# AUDIO_AMP_NB2B.net
KiCad netlist of a schematic drawn in Altium Designer
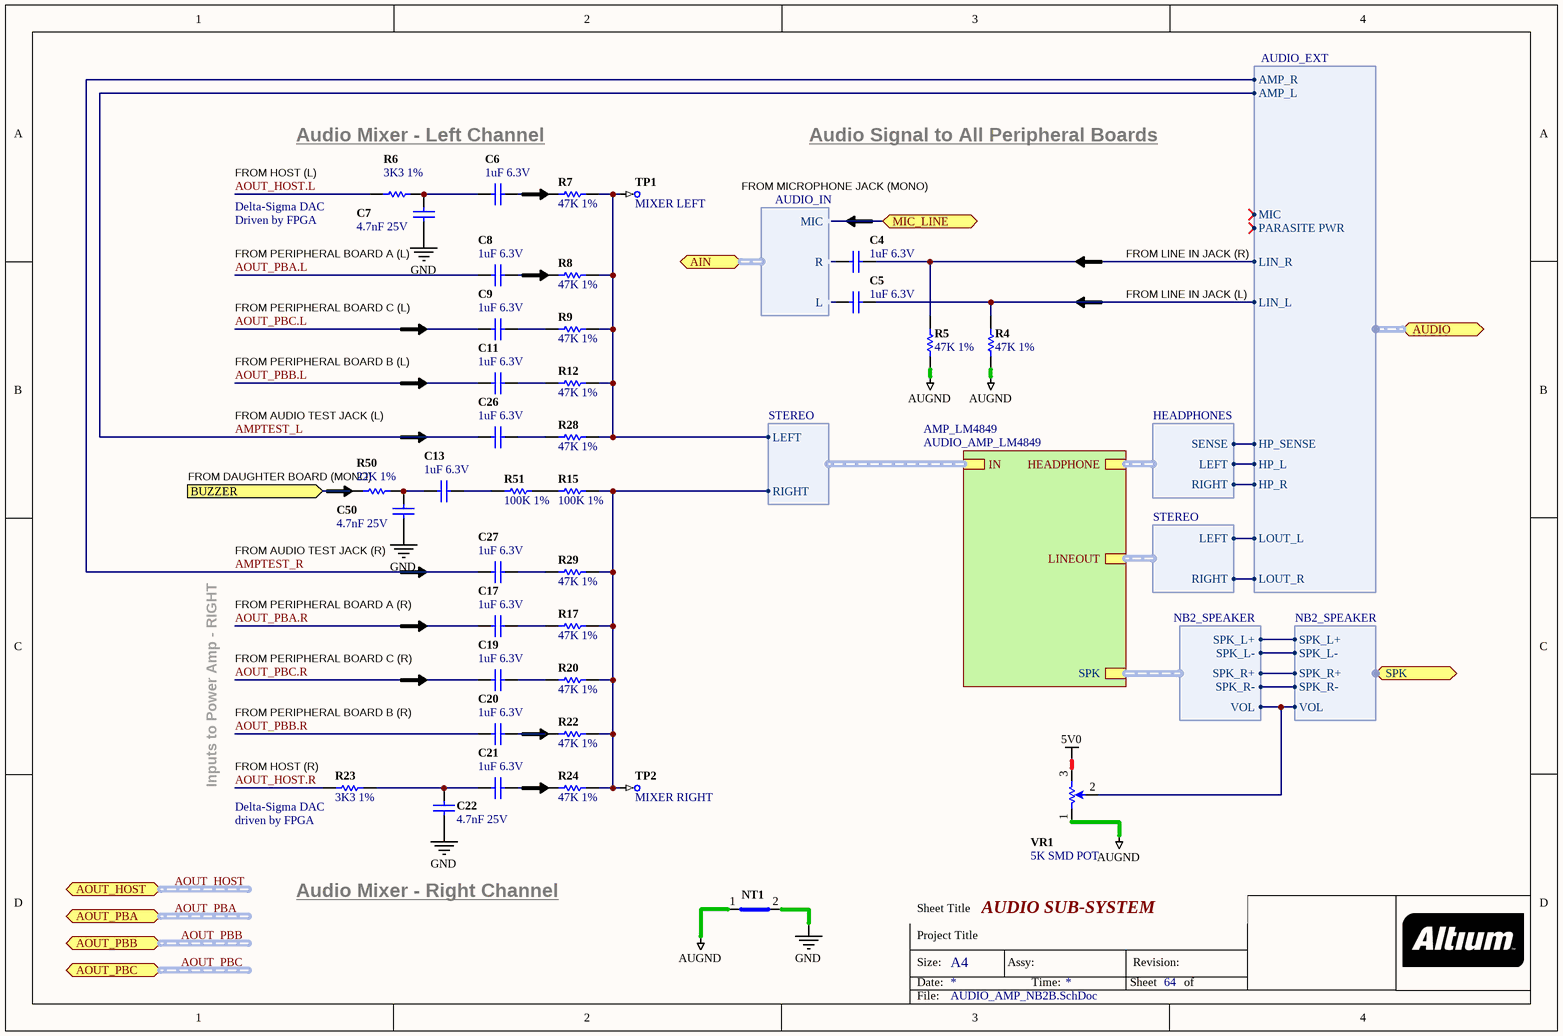
[diagram p0: AUDIO_AMP_NB2B.SchDoc]

(export (version "E")
  (design (tool "Eeschema 10.0.6"))
  (components
    (comp (ref "C4")
      (value "1uF 6.3V")
      (footprint "CAPC1005-STAR")
      (description "Capacitor, Ceramic, 1uF 10% 6.3V 0402 (1005) X5R")
      (fields (field (name "TOLERANCE") "10 %"))
      (libsource (lib "altium-import") (part "root_3_CAP-NP_"))
    )
    (comp (ref "C5")
      (value "1uF 6.3V")
      (footprint "CAPC1005-STAR")
      (description "Capacitor, Ceramic, 1uF 10% 6.3V 0402 (1005) X5R")
      (fields (field (name "TOLERANCE") "10 %"))
      (libsource (lib "altium-import") (part "root_3_CAP-NP_"))
    )
    (comp (ref "C6")
      (value "1uF 6.3V")
      (footprint "CAPC1005-STAR")
      (description "Capacitor, Ceramic, 1uF 10% 6.3V 0402 (1005) X5R")
      (fields (field (name "TOLERANCE") "10 %"))
      (libsource (lib "altium-import") (part "root_3_CAP-NP_"))
    )
    (comp (ref "C7")
      (value "4.7nF 25V")
      (footprint "CAPC1005-STAR")
      (description "Capacitor, Ceramic, 4.7nF 10% 25V 0402 (1005) X7R")
      (fields (field (name "TOLERANCE") "10 %"))
      (libsource (lib "altium-import") (part "root_0_CAP-NP_"))
    )
    (comp (ref "C8")
      (value "1uF 6.3V")
      (footprint "CAPC1005-STAR")
      (description "Capacitor, Ceramic, 1uF 10% 6.3V 0402 (1005) X5R")
      (fields (field (name "TOLERANCE") "10 %"))
      (libsource (lib "altium-import") (part "root_3_CAP-NP_"))
    )
    (comp (ref "C9")
      (value "1uF 6.3V")
      (footprint "CAPC1005-STAR")
      (description "Capacitor, Ceramic, 1uF 10% 6.3V 0402 (1005) X5R")
      (fields (field (name "TOLERANCE") "10 %"))
      (libsource (lib "altium-import") (part "root_3_CAP-NP_"))
    )
    (comp (ref "C11")
      (value "1uF 6.3V")
      (footprint "CAPC1005-STAR")
      (description "Capacitor, Ceramic, 1uF 10% 6.3V 0402 (1005) X5R")
      (fields (field (name "TOLERANCE") "10 %"))
      (libsource (lib "altium-import") (part "root_3_CAP-NP_"))
    )
    (comp (ref "C13")
      (value "1uF 6.3V")
      (footprint "CAPC1005-STAR")
      (description "Capacitor, Ceramic, 1uF 10% 6.3V 0402 (1005) X5R")
      (fields (field (name "TOLERANCE") "10 %"))
      (libsource (lib "altium-import") (part "root_3_CAP-NP_"))
    )
    (comp (ref "C17")
      (value "1uF 6.3V")
      (footprint "CAPC1005-STAR")
      (description "Capacitor, Ceramic, 1uF 10% 6.3V 0402 (1005) X5R")
      (fields (field (name "TOLERANCE") "10 %"))
      (libsource (lib "altium-import") (part "root_3_CAP-NP_"))
    )
    (comp (ref "C19")
      (value "1uF 6.3V")
      (footprint "CAPC1005-STAR")
      (description "Capacitor, Ceramic, 1uF 10% 6.3V 0402 (1005) X5R")
      (fields (field (name "TOLERANCE") "10 %"))
      (libsource (lib "altium-import") (part "root_3_CAP-NP_"))
    )
    (comp (ref "C20")
      (value "1uF 6.3V")
      (footprint "CAPC1005-STAR")
      (description "Capacitor, Ceramic, 1uF 10% 6.3V 0402 (1005) X5R")
      (fields (field (name "TOLERANCE") "10 %"))
      (libsource (lib "altium-import") (part "root_3_CAP-NP_"))
    )
    (comp (ref "C21")
      (value "1uF 6.3V")
      (footprint "CAPC1005-STAR")
      (description "Capacitor, Ceramic, 1uF 10% 6.3V 0402 (1005) X5R")
      (fields (field (name "TOLERANCE") "10 %"))
      (libsource (lib "altium-import") (part "root_3_CAP-NP_"))
    )
    (comp (ref "C22")
      (value "4.7nF 25V")
      (footprint "CAPC1005-STAR")
      (description "Capacitor, Ceramic, 4.7nF 10% 25V 0402 (1005) X7R")
      (fields (field (name "TOLERANCE") "10 %"))
      (libsource (lib "altium-import") (part "root_0_CAP-NP_"))
    )
    (comp (ref "C26")
      (value "1uF 6.3V")
      (footprint "CAPC1005-STAR")
      (description "Capacitor, Ceramic, 1uF 10% 6.3V 0402 (1005) X5R")
      (fields (field (name "TOLERANCE") "10 %"))
      (libsource (lib "altium-import") (part "root_3_CAP-NP_"))
    )
    (comp (ref "C27")
      (value "1uF 6.3V")
      (footprint "CAPC1005-STAR")
      (description "Capacitor, Ceramic, 1uF 10% 6.3V 0402 (1005) X5R")
      (fields (field (name "TOLERANCE") "10 %"))
      (libsource (lib "altium-import") (part "root_3_CAP-NP_"))
    )
    (comp (ref "C50")
      (value "4.7nF 25V")
      (footprint "CAPC1005-STAR")
      (description "Capacitor, Ceramic, 4.7nF 10% 25V 0402 (1005) X7R")
      (fields (field (name "TOLERANCE") "10 %"))
      (libsource (lib "altium-import") (part "root_0_CAP-NP_"))
    )
    (comp (ref "NT1")
      (value "Net Tie SMT2")
      (footprint "NETTIE-SMT2-31X39")
      (description "Net-Tie, Surface Mount, 2 x 2.0mm x 0.8mm SMT Pads - For 0.8mm Track")
      (libsource (lib "AltiumDesignLibrary") (part "NETTIE-SMT2"))
    )
    (comp (ref "R4")
      (value "47K 1%")
      (footprint "RESC1005-STAR")
      (description "Resistor, 47K 1% 0402 (1005)")
      (fields (field (name "TOLERANCE") "1 %"))
      (libsource (lib "altium-import") (part "root_2_RES_"))
    )
    (comp (ref "R5")
      (value "47K 1%")
      (footprint "RESC1005-STAR")
      (description "Resistor, 47K 1% 0402 (1005)")
      (fields (field (name "TOLERANCE") "1 %"))
      (libsource (lib "altium-import") (part "root_2_RES_"))
    )
    (comp (ref "R6")
      (value "3K3 1%")
      (footprint "RESC1005-STAR")
      (description "Resistor, 3K3 1% 0402 (1005)")
      (fields (field (name "TOLERANCE") "1 %"))
      (libsource (lib "altium-import") (part "root_1_RES_"))
    )
    (comp (ref "R7")
      (value "47K 1%")
      (footprint "RESC1005-STAR")
      (description "Resistor, 47K 1% 0402 (1005)")
      (fields (field (name "TOLERANCE") "1 %"))
      (libsource (lib "altium-import") (part "root_1_RES_"))
    )
    (comp (ref "R8")
      (value "47K 1%")
      (footprint "RESC1005-STAR")
      (description "Resistor, 47K 1% 0402 (1005)")
      (fields (field (name "TOLERANCE") "1 %"))
      (libsource (lib "altium-import") (part "root_1_RES_"))
    )
    (comp (ref "R9")
      (value "47K 1%")
      (footprint "RESC1005-STAR")
      (description "Resistor, 47K 1% 0402 (1005)")
      (fields (field (name "TOLERANCE") "1 %"))
      (libsource (lib "altium-import") (part "root_1_RES_"))
    )
    (comp (ref "R12")
      (value "47K 1%")
      (footprint "RESC1005-STAR")
      (description "Resistor, 47K 1% 0402 (1005)")
      (fields (field (name "TOLERANCE") "1 %"))
      (libsource (lib "altium-import") (part "root_1_RES_"))
    )
    (comp (ref "R15")
      (value "100K 1%")
      (footprint "RESC1005-STAR")
      (description "Resistor, 100K 1% 0402 (1005)")
      (fields (field (name "TOLERANCE") "1 %"))
      (libsource (lib "altium-import") (part "root_1_RES_"))
    )
    (comp (ref "R17")
      (value "47K 1%")
      (footprint "RESC1005-STAR")
      (description "Resistor, 47K 1% 0402 (1005)")
      (fields (field (name "TOLERANCE") "1 %"))
      (libsource (lib "altium-import") (part "root_1_RES_"))
    )
    (comp (ref "R20")
      (value "47K 1%")
      (footprint "RESC1005-STAR")
      (description "Resistor, 47K 1% 0402 (1005)")
      (fields (field (name "TOLERANCE") "1 %"))
      (libsource (lib "altium-import") (part "root_1_RES_"))
    )
    (comp (ref "R22")
      (value "47K 1%")
      (footprint "RESC1005-STAR")
      (description "Resistor, 47K 1% 0402 (1005)")
      (fields (field (name "TOLERANCE") "1 %"))
      (libsource (lib "altium-import") (part "root_1_RES_"))
    )
    (comp (ref "R23")
      (value "3K3 1%")
      (footprint "RESC1005-STAR")
      (description "Resistor, 3K3 1% 0402 (1005)")
      (fields (field (name "TOLERANCE") "1 %"))
      (libsource (lib "altium-import") (part "root_1_RES_"))
    )
    (comp (ref "R24")
      (value "47K 1%")
      (footprint "RESC1005-STAR")
      (description "Resistor, 47K 1% 0402 (1005)")
      (fields (field (name "TOLERANCE") "1 %"))
      (libsource (lib "altium-import") (part "root_1_RES_"))
    )
    (comp (ref "R28")
      (value "47K 1%")
      (footprint "RESC1005-STAR")
      (description "Resistor, 47K 1% 0402 (1005)")
      (fields (field (name "TOLERANCE") "1 %"))
      (libsource (lib "altium-import") (part "root_1_RES_"))
    )
    (comp (ref "R29")
      (value "47K 1%")
      (footprint "RESC1005-STAR")
      (description "Resistor, 47K 1% 0402 (1005)")
      (fields (field (name "TOLERANCE") "1 %"))
      (libsource (lib "altium-import") (part "root_1_RES_"))
    )
    (comp (ref "R50")
      (value "22K 1%")
      (footprint "RESC1005-STAR")
      (description "Resistor, 22K 1% 0402 (1005)")
      (fields (field (name "TOLERANCE") "1 %"))
      (libsource (lib "altium-import") (part "root_1_RES_"))
    )
    (comp (ref "R51")
      (value "100K 1%")
      (footprint "RESC1005-STAR")
      (description "Resistor, 100K 1% 0402 (1005)")
      (fields (field (name "TOLERANCE") "1 %"))
      (libsource (lib "altium-import") (part "root_1_RES_"))
    )
    (comp (ref "TP1")
      (value "MIXER LEFT")
      (footprint "TestPin")
      (description "Test Point, PCB Mount with Silkscreen Box")
      (libsource (lib "AltiumDesignLibrary") (part "TestPin"))
    )
    (comp (ref "TP2")
      (value "MIXER RIGHT")
      (footprint "TestPin")
      (description "Test Point, PCB Mount with Silkscreen Box")
      (libsource (lib "AltiumDesignLibrary") (part "TestPin"))
    )
    (comp (ref "VR1")
      (value "5K SMD POT")
      (footprint "TRIMMER_3361")
      (description "Potentiometer, SMD, 3361 Side Entry, Single Turn")
      (libsource (lib "AltiumDesignLibrary") (part "POT"))
    )
  )
  (nets
    (net (code "10") (name "/AMPTEST_L") (class "Default")
      (node (ref "C26") (pin "2") (pinfunction "2_2") (pintype "passive"))
    )
    (net (code "11") (name "/AMPTEST_R") (class "Default")
      (node (ref "C27") (pin "2") (pinfunction "2_2") (pintype "passive"))
    )
    (net (code "12") (name "/AOUT_HOST.L") (class "Default")
      (node (ref "R6") (pin "1") (pinfunction "1_1") (pintype "passive"))
    )
    (net (code "13") (name "/AOUT_HOST.R") (class "Default")
      (node (ref "R23") (pin "1") (pinfunction "1_1") (pintype "passive"))
    )
    (net (code "14") (name "/AOUT_PBA.L") (class "Default")
      (node (ref "C8") (pin "2") (pinfunction "2_2") (pintype "passive"))
    )
    (net (code "15") (name "/AOUT_PBA.R") (class "Default")
      (node (ref "C17") (pin "2") (pinfunction "2_2") (pintype "passive"))
    )
    (net (code "16") (name "/AOUT_PBB.L") (class "Default")
      (node (ref "C11") (pin "2") (pinfunction "2_2") (pintype "passive"))
    )
    (net (code "17") (name "/AOUT_PBB.R") (class "Default")
      (node (ref "C20") (pin "2") (pinfunction "2_2") (pintype "passive"))
    )
    (net (code "18") (name "/AOUT_PBC.L") (class "Default")
      (node (ref "C9") (pin "2") (pinfunction "2_2") (pintype "passive"))
    )
    (net (code "19") (name "/AOUT_PBC.R") (class "Default")
      (node (ref "C19") (pin "2") (pinfunction "2_2") (pintype "passive"))
    )
    (net (code "20") (name "/BUZZER") (class "Default")
      (node (ref "R50") (pin "1") (pinfunction "1_1") (pintype "passive"))
    )
    (net (code "24") (name "/L") (class "Default")
      (node (ref "C5") (pin "2") (pinfunction "2_2") (pintype "passive"))
    )
    (net (code "25") (name "/LIN_L") (class "Default")
      (node (ref "C5") (pin "1") (pinfunction "1_1") (pintype "passive"))
      (node (ref "R4") (pin "2") (pinfunction "2_2") (pintype "passive"))
    )
    (net (code "26") (name "/LIN_R") (class "Default")
      (node (ref "C4") (pin "1") (pinfunction "1_1") (pintype "passive"))
      (node (ref "R5") (pin "2") (pinfunction "2_2") (pintype "passive"))
    )
    (net (code "30") (name "/R") (class "Default")
      (node (ref "C4") (pin "2") (pinfunction "2_2") (pintype "passive"))
    )
    (net (code "35") (name "/VOL") (class "Default")
      (node (ref "VR1") (pin "2") (pinfunction "2_2") (pintype "passive"))
    )
    (net (code "45") (name "5V0") (class "Default")
      (node (ref "VR1") (pin "3") (pinfunction "3_3") (pintype "passive"))
    )
    (net (code "46") (name "AUGND") (class "Default")
      (node (ref "NT1") (pin "1") (pinfunction "Net1_1") (pintype "passive"))
      (node (ref "R4") (pin "1") (pinfunction "1_1") (pintype "passive"))
      (node (ref "R5") (pin "1") (pinfunction "1_1") (pintype "passive"))
      (node (ref "VR1") (pin "1") (pinfunction "1_1") (pintype "passive"))
    )
    (net (code "47") (name "GND") (class "Default")
      (node (ref "C22") (pin "2") (pinfunction "2_2") (pintype "passive"))
      (node (ref "C50") (pin "2") (pinfunction "2_2") (pintype "passive"))
      (node (ref "C7") (pin "2") (pinfunction "2_2") (pintype "passive"))
      (node (ref "NT1") (pin "2") (pinfunction "Net2_2") (pintype "passive"))
    )
    (net (code "48") (name "Net-(C6-Pad1)") (class "Default")
      (node (ref "C6") (pin "1") (pinfunction "1_1") (pintype "passive"))
      (node (ref "R7") (pin "1") (pinfunction "1_1") (pintype "passive"))
    )
    (net (code "49") (name "Net-(C6-Pad2)") (class "Default")
      (node (ref "C6") (pin "2") (pinfunction "2_2") (pintype "passive"))
      (node (ref "C7") (pin "1") (pinfunction "1_1") (pintype "passive"))
      (node (ref "R6") (pin "2") (pinfunction "2_2") (pintype "passive"))
    )
    (net (code "50") (name "Net-(C8-Pad1)") (class "Default")
      (node (ref "C8") (pin "1") (pinfunction "1_1") (pintype "passive"))
      (node (ref "R8") (pin "1") (pinfunction "1_1") (pintype "passive"))
    )
    (net (code "51") (name "Net-(C9-Pad1)") (class "Default")
      (node (ref "C9") (pin "1") (pinfunction "1_1") (pintype "passive"))
      (node (ref "R9") (pin "1") (pinfunction "1_1") (pintype "passive"))
    )
    (net (code "52") (name "Net-(C11-Pad1)") (class "Default")
      (node (ref "C11") (pin "1") (pinfunction "1_1") (pintype "passive"))
      (node (ref "R12") (pin "1") (pinfunction "1_1") (pintype "passive"))
    )
    (net (code "53") (name "Net-(C13-Pad1)") (class "Default")
      (node (ref "C13") (pin "1") (pinfunction "1_1") (pintype "passive"))
      (node (ref "R51") (pin "1") (pinfunction "1_1") (pintype "passive"))
    )
    (net (code "54") (name "Net-(C13-Pad2)") (class "Default")
      (node (ref "C13") (pin "2") (pinfunction "2_2") (pintype "passive"))
      (node (ref "C50") (pin "1") (pinfunction "1_1") (pintype "passive"))
      (node (ref "R50") (pin "2") (pinfunction "2_2") (pintype "passive"))
    )
    (net (code "55") (name "Net-(C17-Pad1)") (class "Default")
      (node (ref "C17") (pin "1") (pinfunction "1_1") (pintype "passive"))
      (node (ref "R17") (pin "1") (pinfunction "1_1") (pintype "passive"))
    )
    (net (code "56") (name "Net-(C19-Pad1)") (class "Default")
      (node (ref "C19") (pin "1") (pinfunction "1_1") (pintype "passive"))
      (node (ref "R20") (pin "1") (pinfunction "1_1") (pintype "passive"))
    )
    (net (code "57") (name "Net-(C20-Pad1)") (class "Default")
      (node (ref "C20") (pin "1") (pinfunction "1_1") (pintype "passive"))
      (node (ref "R22") (pin "1") (pinfunction "1_1") (pintype "passive"))
    )
    (net (code "58") (name "Net-(C21-Pad1)") (class "Default")
      (node (ref "C21") (pin "1") (pinfunction "1_1") (pintype "passive"))
      (node (ref "R24") (pin "1") (pinfunction "1_1") (pintype "passive"))
    )
    (net (code "59") (name "Net-(C21-Pad2)") (class "Default")
      (node (ref "C21") (pin "2") (pinfunction "2_2") (pintype "passive"))
      (node (ref "C22") (pin "1") (pinfunction "1_1") (pintype "passive"))
      (node (ref "R23") (pin "2") (pinfunction "2_2") (pintype "passive"))
    )
    (net (code "60") (name "Net-(C26-Pad1)") (class "Default")
      (node (ref "C26") (pin "1") (pinfunction "1_1") (pintype "passive"))
      (node (ref "R28") (pin "1") (pinfunction "1_1") (pintype "passive"))
    )
    (net (code "61") (name "Net-(C27-Pad1)") (class "Default")
      (node (ref "C27") (pin "1") (pinfunction "1_1") (pintype "passive"))
      (node (ref "R29") (pin "1") (pinfunction "1_1") (pintype "passive"))
    )
    (net (code "62") (name "Net-(R12-Pad2)") (class "Default")
      (node (ref "R12") (pin "2") (pinfunction "2_2") (pintype "passive"))
      (node (ref "R28") (pin "2") (pinfunction "2_2") (pintype "passive"))
      (node (ref "R7") (pin "2") (pinfunction "2_2") (pintype "passive"))
      (node (ref "R8") (pin "2") (pinfunction "2_2") (pintype "passive"))
      (node (ref "R9") (pin "2") (pinfunction "2_2") (pintype "passive"))
      (node (ref "TP1") (pin "1") (pinfunction "1_1") (pintype "input"))
    )
    (net (code "63") (name "Net-(R15-Pad1)") (class "Default")
      (node (ref "R15") (pin "1") (pinfunction "1_1") (pintype "passive"))
      (node (ref "R51") (pin "2") (pinfunction "2_2") (pintype "passive"))
    )
    (net (code "64") (name "Net-(R15-Pad2)") (class "Default")
      (node (ref "R15") (pin "2") (pinfunction "2_2") (pintype "passive"))
      (node (ref "R17") (pin "2") (pinfunction "2_2") (pintype "passive"))
      (node (ref "R20") (pin "2") (pinfunction "2_2") (pintype "passive"))
      (node (ref "R22") (pin "2") (pinfunction "2_2") (pintype "passive"))
      (node (ref "R24") (pin "2") (pinfunction "2_2") (pintype "passive"))
      (node (ref "R29") (pin "2") (pinfunction "2_2") (pintype "passive"))
      (node (ref "TP2") (pin "1") (pinfunction "1_1") (pintype "input"))
    )
  )
)
